# Antenna_Connectors.net
KiCad netlist of a schematic drawn in Altium Designer
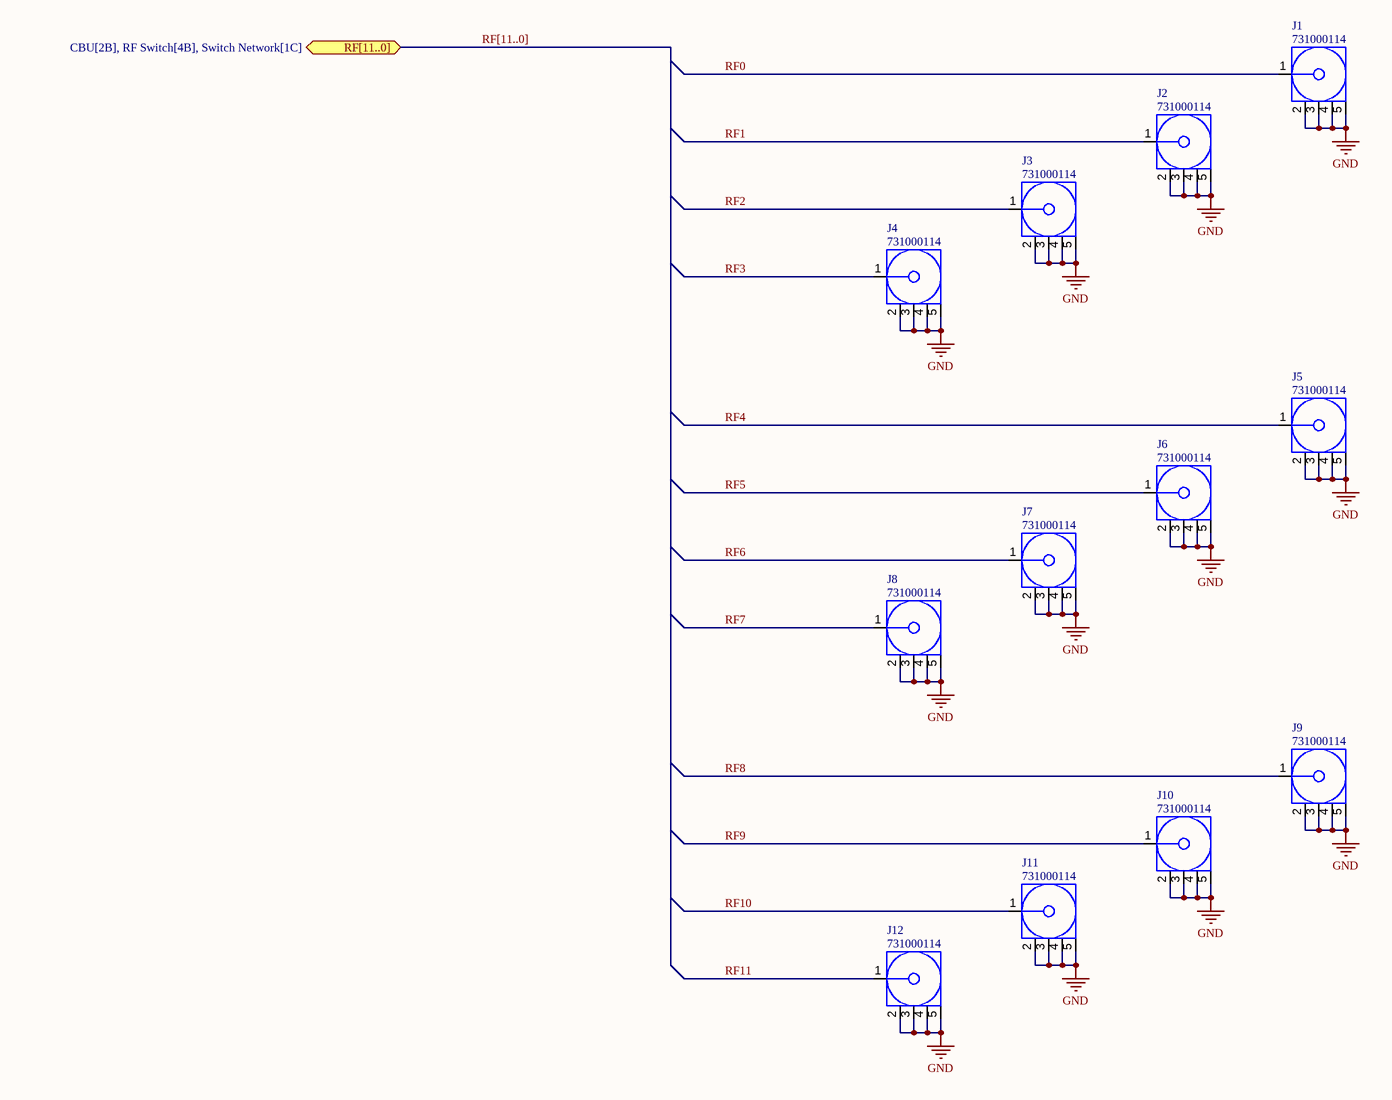
[diagram p0: Antenna Connectors.SchDoc]

(export (version "E")
  (design (tool "Eeschema 10.0.6"))
  (components
    (comp (ref "J1")
      (value "731000114")
      (footprint "731000114_V")
      (description "SMA Right-Angle PCB Jack Receptacle, Brass Body, Gold Plated, 50 Ohm, 5-Pin THD, RoHS, Tray")
      (fields (field (name "MANUFACTURER") "Molex"))
      (libsource (lib "CBU-PCB") (part "731000114"))
    )
    (comp (ref "J2")
      (value "731000114")
      (footprint "731000114_V")
      (description "SMA Right-Angle PCB Jack Receptacle, Brass Body, Gold Plated, 50 Ohm, 5-Pin THD, RoHS, Tray")
      (fields (field (name "MANUFACTURER") "Molex"))
      (libsource (lib "CBU-PCB") (part "731000114"))
    )
    (comp (ref "J3")
      (value "731000114")
      (footprint "731000114_V")
      (description "SMA Right-Angle PCB Jack Receptacle, Brass Body, Gold Plated, 50 Ohm, 5-Pin THD, RoHS, Tray")
      (fields (field (name "MANUFACTURER") "Molex"))
      (libsource (lib "CBU-PCB") (part "731000114"))
    )
    (comp (ref "J4")
      (value "731000114")
      (footprint "731000114_V")
      (description "SMA Right-Angle PCB Jack Receptacle, Brass Body, Gold Plated, 50 Ohm, 5-Pin THD, RoHS, Tray")
      (fields (field (name "MANUFACTURER") "Molex"))
      (libsource (lib "CBU-PCB") (part "731000114"))
    )
    (comp (ref "J5")
      (value "731000114")
      (footprint "731000114_V")
      (description "SMA Right-Angle PCB Jack Receptacle, Brass Body, Gold Plated, 50 Ohm, 5-Pin THD, RoHS, Tray")
      (fields (field (name "MANUFACTURER") "Molex"))
      (libsource (lib "CBU-PCB") (part "731000114"))
    )
    (comp (ref "J6")
      (value "731000114")
      (footprint "731000114_V")
      (description "SMA Right-Angle PCB Jack Receptacle, Brass Body, Gold Plated, 50 Ohm, 5-Pin THD, RoHS, Tray")
      (fields (field (name "MANUFACTURER") "Molex"))
      (libsource (lib "CBU-PCB") (part "731000114"))
    )
    (comp (ref "J7")
      (value "731000114")
      (footprint "731000114_V")
      (description "SMA Right-Angle PCB Jack Receptacle, Brass Body, Gold Plated, 50 Ohm, 5-Pin THD, RoHS, Tray")
      (fields (field (name "MANUFACTURER") "Molex"))
      (libsource (lib "CBU-PCB") (part "731000114"))
    )
    (comp (ref "J8")
      (value "731000114")
      (footprint "731000114_V")
      (description "SMA Right-Angle PCB Jack Receptacle, Brass Body, Gold Plated, 50 Ohm, 5-Pin THD, RoHS, Tray")
      (fields (field (name "MANUFACTURER") "Molex"))
      (libsource (lib "CBU-PCB") (part "731000114"))
    )
    (comp (ref "J9")
      (value "731000114")
      (footprint "731000114_V")
      (description "SMA Right-Angle PCB Jack Receptacle, Brass Body, Gold Plated, 50 Ohm, 5-Pin THD, RoHS, Tray")
      (fields (field (name "MANUFACTURER") "Molex"))
      (libsource (lib "CBU-PCB") (part "731000114"))
    )
    (comp (ref "J10")
      (value "731000114")
      (footprint "731000114_V")
      (description "SMA Right-Angle PCB Jack Receptacle, Brass Body, Gold Plated, 50 Ohm, 5-Pin THD, RoHS, Tray")
      (fields (field (name "MANUFACTURER") "Molex"))
      (libsource (lib "CBU-PCB") (part "731000114"))
    )
    (comp (ref "J11")
      (value "731000114")
      (footprint "731000114_V")
      (description "SMA Right-Angle PCB Jack Receptacle, Brass Body, Gold Plated, 50 Ohm, 5-Pin THD, RoHS, Tray")
      (fields (field (name "MANUFACTURER") "Molex"))
      (libsource (lib "CBU-PCB") (part "731000114"))
    )
    (comp (ref "J12")
      (value "731000114")
      (footprint "731000114_V")
      (description "SMA Right-Angle PCB Jack Receptacle, Brass Body, Gold Plated, 50 Ohm, 5-Pin THD, RoHS, Tray")
      (fields (field (name "MANUFACTURER") "Molex"))
      (libsource (lib "CBU-PCB") (part "731000114"))
    )
  )
  (nets
    (net (code "1") (name "/RF0") (class "Default")
      (node (ref "J1") (pin "1") (pinfunction "1_1") (pintype "passive"))
    )
    (net (code "2") (name "/RF1") (class "Default")
      (node (ref "J2") (pin "1") (pinfunction "1_1") (pintype "passive"))
    )
    (net (code "3") (name "/RF2") (class "Default")
      (node (ref "J3") (pin "1") (pinfunction "1_1") (pintype "passive"))
    )
    (net (code "4") (name "/RF3") (class "Default")
      (node (ref "J4") (pin "1") (pinfunction "1_1") (pintype "passive"))
    )
    (net (code "5") (name "/RF4") (class "Default")
      (node (ref "J5") (pin "1") (pinfunction "1_1") (pintype "passive"))
    )
    (net (code "6") (name "/RF5") (class "Default")
      (node (ref "J6") (pin "1") (pinfunction "1_1") (pintype "passive"))
    )
    (net (code "7") (name "/RF6") (class "Default")
      (node (ref "J7") (pin "1") (pinfunction "1_1") (pintype "passive"))
    )
    (net (code "8") (name "/RF7") (class "Default")
      (node (ref "J8") (pin "1") (pinfunction "1_1") (pintype "passive"))
    )
    (net (code "9") (name "/RF8") (class "Default")
      (node (ref "J9") (pin "1") (pinfunction "1_1") (pintype "passive"))
    )
    (net (code "10") (name "/RF9") (class "Default")
      (node (ref "J10") (pin "1") (pinfunction "1_1") (pintype "passive"))
    )
    (net (code "11") (name "/RF10") (class "Default")
      (node (ref "J11") (pin "1") (pinfunction "1_1") (pintype "passive"))
    )
    (net (code "12") (name "/RF11") (class "Default")
      (node (ref "J12") (pin "1") (pinfunction "1_1") (pintype "passive"))
    )
    (net (code "14") (name "GND") (class "Default")
      (node (ref "J1") (pin "2") (pinfunction "2_2") (pintype "passive"))
      (node (ref "J1") (pin "3") (pinfunction "3_3") (pintype "passive"))
      (node (ref "J1") (pin "4") (pinfunction "4_4") (pintype "passive"))
      (node (ref "J1") (pin "5") (pinfunction "5_5") (pintype "passive"))
      (node (ref "J10") (pin "2") (pinfunction "2_2") (pintype "passive"))
      (node (ref "J10") (pin "3") (pinfunction "3_3") (pintype "passive"))
      (node (ref "J10") (pin "4") (pinfunction "4_4") (pintype "passive"))
      (node (ref "J10") (pin "5") (pinfunction "5_5") (pintype "passive"))
      (node (ref "J11") (pin "2") (pinfunction "2_2") (pintype "passive"))
      (node (ref "J11") (pin "3") (pinfunction "3_3") (pintype "passive"))
      (node (ref "J11") (pin "4") (pinfunction "4_4") (pintype "passive"))
      (node (ref "J11") (pin "5") (pinfunction "5_5") (pintype "passive"))
      (node (ref "J12") (pin "2") (pinfunction "2_2") (pintype "passive"))
      (node (ref "J12") (pin "3") (pinfunction "3_3") (pintype "passive"))
      (node (ref "J12") (pin "4") (pinfunction "4_4") (pintype "passive"))
      (node (ref "J12") (pin "5") (pinfunction "5_5") (pintype "passive"))
      (node (ref "J2") (pin "2") (pinfunction "2_2") (pintype "passive"))
      (node (ref "J2") (pin "3") (pinfunction "3_3") (pintype "passive"))
      (node (ref "J2") (pin "4") (pinfunction "4_4") (pintype "passive"))
      (node (ref "J2") (pin "5") (pinfunction "5_5") (pintype "passive"))
      (node (ref "J3") (pin "2") (pinfunction "2_2") (pintype "passive"))
      (node (ref "J3") (pin "3") (pinfunction "3_3") (pintype "passive"))
      (node (ref "J3") (pin "4") (pinfunction "4_4") (pintype "passive"))
      (node (ref "J3") (pin "5") (pinfunction "5_5") (pintype "passive"))
      (node (ref "J4") (pin "2") (pinfunction "2_2") (pintype "passive"))
      (node (ref "J4") (pin "3") (pinfunction "3_3") (pintype "passive"))
      (node (ref "J4") (pin "4") (pinfunction "4_4") (pintype "passive"))
      (node (ref "J4") (pin "5") (pinfunction "5_5") (pintype "passive"))
      (node (ref "J5") (pin "2") (pinfunction "2_2") (pintype "passive"))
      (node (ref "J5") (pin "3") (pinfunction "3_3") (pintype "passive"))
      (node (ref "J5") (pin "4") (pinfunction "4_4") (pintype "passive"))
      (node (ref "J5") (pin "5") (pinfunction "5_5") (pintype "passive"))
      (node (ref "J6") (pin "2") (pinfunction "2_2") (pintype "passive"))
      (node (ref "J6") (pin "3") (pinfunction "3_3") (pintype "passive"))
      (node (ref "J6") (pin "4") (pinfunction "4_4") (pintype "passive"))
      (node (ref "J6") (pin "5") (pinfunction "5_5") (pintype "passive"))
      (node (ref "J7") (pin "2") (pinfunction "2_2") (pintype "passive"))
      (node (ref "J7") (pin "3") (pinfunction "3_3") (pintype "passive"))
      (node (ref "J7") (pin "4") (pinfunction "4_4") (pintype "passive"))
      (node (ref "J7") (pin "5") (pinfunction "5_5") (pintype "passive"))
      (node (ref "J8") (pin "2") (pinfunction "2_2") (pintype "passive"))
      (node (ref "J8") (pin "3") (pinfunction "3_3") (pintype "passive"))
      (node (ref "J8") (pin "4") (pinfunction "4_4") (pintype "passive"))
      (node (ref "J8") (pin "5") (pinfunction "5_5") (pintype "passive"))
      (node (ref "J9") (pin "2") (pinfunction "2_2") (pintype "passive"))
      (node (ref "J9") (pin "3") (pinfunction "3_3") (pintype "passive"))
      (node (ref "J9") (pin "4") (pinfunction "4_4") (pintype "passive"))
      (node (ref "J9") (pin "5") (pinfunction "5_5") (pintype "passive"))
    )
  )
)
